# Un_Battery_old.net
KiCad netlist of a schematic drawn in EAGLE
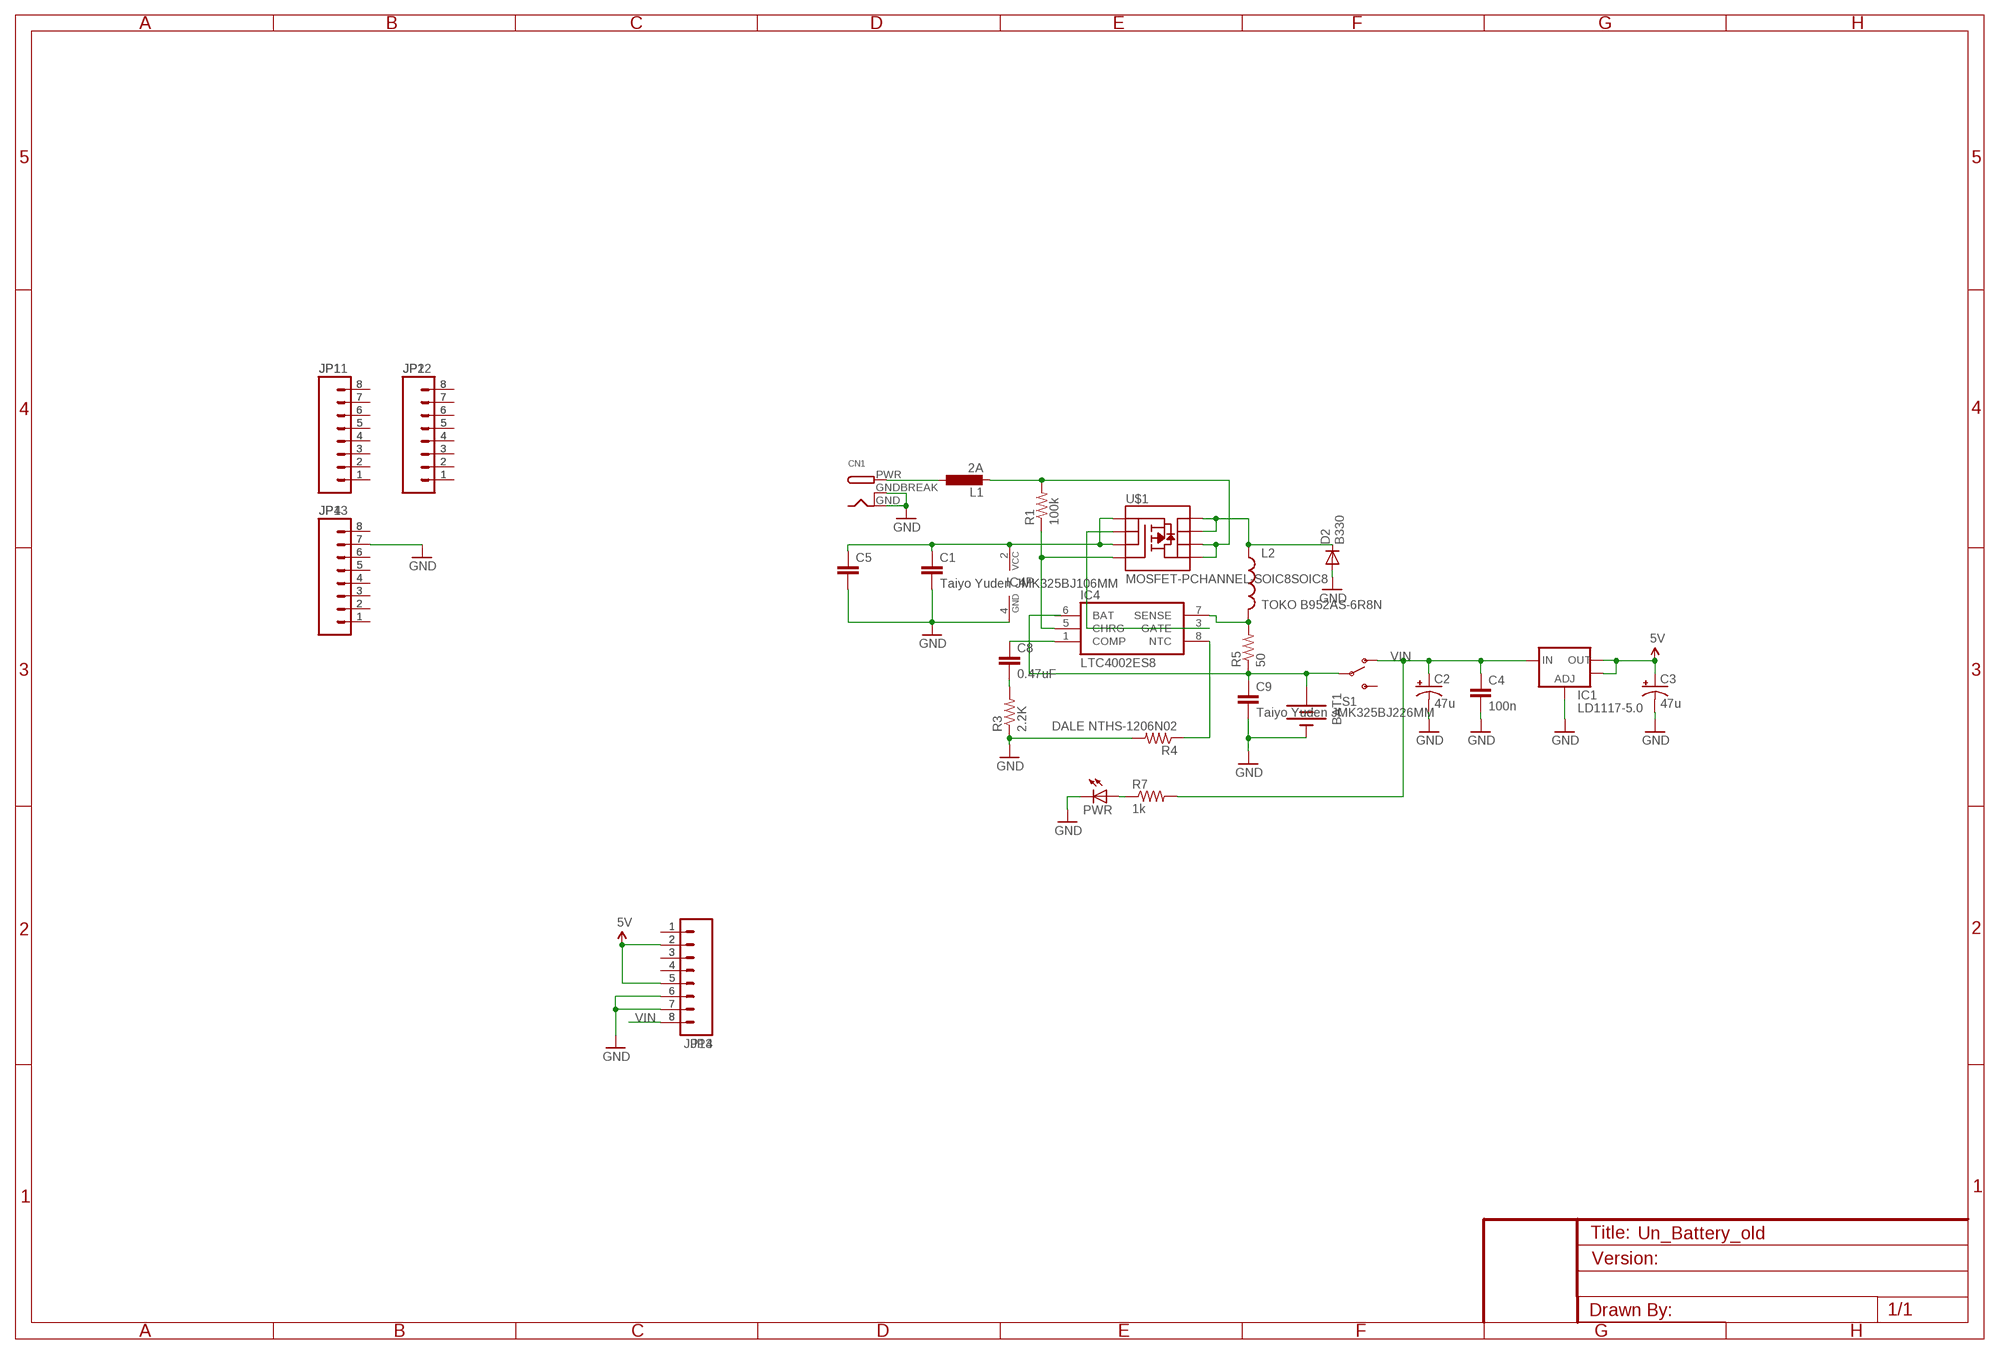
[diagram p0: schematic, sheet 1]

(export (version "E")
  (design (tool "Eeschema 10.0.6"))
  (components
    (comp (ref "BAT1")
      (value "BATTERYLIPO")
      (footprint "eagle-import:BATTERY-LIPO")
      (libsource (lib "eagle-import") (part "BATTERYLIPO"))
    )
    (comp (ref "C1")
      (value "Taiyo Yuden JMK325BJ106MM")
      (footprint "eagle-import:1206")
      (libsource (lib "eagle-import") (part "2SparkFun_CAP1206"))
    )
    (comp (ref "C2")
      (value "47u")
      (footprint "eagle-import:PANASONIC_D")
      (libsource (lib "eagle-import") (part "CAP_POLD"))
    )
    (comp (ref "C3")
      (value "47u")
      (footprint "eagle-import:PANASONIC_D")
      (libsource (lib "eagle-import") (part "CAP_POLD"))
    )
    (comp (ref "C4")
      (value "100n")
      (footprint "eagle-import:0603-CAP")
      (libsource (lib "eagle-import") (part "CAP0603-CAP"))
    )
    (comp (ref "C5")
      (value "CAP1206")
      (footprint "eagle-import:1206")
      (libsource (lib "eagle-import") (part "2SparkFun_CAP1206"))
    )
    (comp (ref "C8")
      (value "0.47uF")
      (footprint "eagle-import:1206")
      (libsource (lib "eagle-import") (part "2SparkFun_CAP1206"))
    )
    (comp (ref "C9")
      (value "Taiyo Yuden JMK325BJ226MM")
      (footprint "eagle-import:1206")
      (libsource (lib "eagle-import") (part "2SparkFun_CAP1206"))
    )
    (comp (ref "CN1")
      (value "DCBARRELPTH")
      (footprint "eagle-import:DCJACK_2MM_PTH")
      (libsource (lib "eagle-import") (part "DCBARRELPTH"))
    )
    (comp (ref "D2")
      (value "B330")
      (footprint "eagle-import:SMA-DIODE")
      (libsource (lib "eagle-import") (part "DIODESMA"))
    )
    (comp (ref "IC1")
      (value "LD1117-5.0")
      (footprint "eagle-import:SOT223")
      (libsource (lib "eagle-import") (part "V_REG_LM1117SOT223"))
    )
    (comp (ref "IC4")
      (value "LTC4002ES8")
      (footprint "eagle-import:SO08")
      (libsource (lib "eagle-import") (part "LTC4002S8E"))
    )
    (comp (ref "JP1")
      (value "M08SMD")
      (footprint "eagle-import:1X08-SMD")
      (libsource (lib "eagle-import") (part "M08SMD"))
    )
    (comp (ref "JP2")
      (value "M08SMD")
      (footprint "eagle-import:1X08-SMD")
      (libsource (lib "eagle-import") (part "M08SMD"))
    )
    (comp (ref "JP3")
      (value "M08SMD")
      (footprint "eagle-import:1X08-SMD")
      (libsource (lib "eagle-import") (part "M08SMD"))
    )
    (comp (ref "JP4")
      (value "M08SMD")
      (footprint "eagle-import:1X08-SMD")
      (libsource (lib "eagle-import") (part "M08SMD"))
    )
    (comp (ref "JP11")
      (value "M08SMD")
      (footprint "eagle-import:1X08-SMD")
      (libsource (lib "eagle-import") (part "M08SMD"))
    )
    (comp (ref "JP12")
      (value "M08SMD")
      (footprint "eagle-import:1X08-SMD")
      (libsource (lib "eagle-import") (part "M08SMD"))
    )
    (comp (ref "JP13")
      (value "M08SMD")
      (footprint "eagle-import:1X08-SMD")
      (libsource (lib "eagle-import") (part "M08SMD"))
    )
    (comp (ref "JP14")
      (value "M08SMD")
      (footprint "eagle-import:1X08-SMD")
      (libsource (lib "eagle-import") (part "M08SMD"))
    )
    (comp (ref "L1")
      (value "2A")
      (footprint "eagle-import:L1812")
      (libsource (lib "eagle-import") (part "L-EUL1812"))
    )
    (comp (ref "L2")
      (value "TOKO B952AS-6R8N")
      (footprint "eagle-import:CR75")
      (libsource (lib "eagle-import") (part "INDUCTORCR75"))
    )
    (comp (ref "PWR")
      (value "LED0805")
      (footprint "eagle-import:LED-0805")
      (libsource (lib "eagle-import") (part "LED0805"))
    )
    (comp (ref "R1")
      (value "100k")
      (footprint "eagle-import:1206")
      (libsource (lib "eagle-import") (part "RESISTOR1206"))
    )
    (comp (ref "R3")
      (value "2.2K")
      (footprint "eagle-import:1206")
      (libsource (lib "eagle-import") (part "RESISTOR1206"))
    )
    (comp (ref "R4")
      (value "DALE NTHS-1206N02")
      (footprint "eagle-import:1206")
      (libsource (lib "eagle-import") (part "RESISTOR1206"))
    )
    (comp (ref "R5")
      (value "50")
      (footprint "eagle-import:1206")
      (libsource (lib "eagle-import") (part "RESISTOR1206"))
    )
    (comp (ref "R7")
      (value "1k")
      (footprint "eagle-import:0805")
      (libsource (lib "eagle-import") (part "RESISTOR0805-RES"))
    )
    (comp (ref "S1")
      (value "SWITCH-SPSTSMD2")
      (footprint "eagle-import:SWITCH-SPDT-SMD")
      (libsource (lib "eagle-import") (part "SWITCH-SPSTSMD2"))
    )
    (comp (ref "U$1")
      (value "MOSFET-PCHANNEL-SOIC8SOIC8")
      (footprint "eagle-import:SO08")
      (libsource (lib "eagle-import") (part "MOSFET-PCHANNEL-SOIC8SOIC8"))
    )
  )
  (nets
    (net (code "1") (name "/VIN") (class "Default")
      (node (ref "C2") (pin "+") (pinfunction "+_+") (pintype "passive"))
      (node (ref "C4") (pin "1") (pinfunction "1_1") (pintype "passive"))
      (node (ref "IC1") (pin "3") (pinfunction "IN_3") (pintype "input"))
      (node (ref "JP14") (pin "8") (pinfunction "8_8") (pintype "passive"))
      (node (ref "JP3") (pin "8") (pinfunction "8_8") (pintype "passive"))
      (node (ref "R7") (pin "2") (pinfunction "2_2") (pintype "passive"))
      (node (ref "S1") (pin "1") (pinfunction "O_1") (pintype "passive"))
    )
    (net (code "2") (name "5V") (class "Default")
      (node (ref "C3") (pin "+") (pinfunction "+_+") (pintype "passive"))
      (node (ref "IC1") (pin "2") (pinfunction "OUT_2") (pintype "output"))
      (node (ref "IC1") (pin "4") (pinfunction "OUT_4") (pintype "output"))
      (node (ref "JP14") (pin "2") (pinfunction "2_2") (pintype "passive"))
      (node (ref "JP14") (pin "5") (pinfunction "5_5") (pintype "passive"))
      (node (ref "JP3") (pin "2") (pinfunction "2_2") (pintype "passive"))
      (node (ref "JP3") (pin "5") (pinfunction "5_5") (pintype "passive"))
    )
    (net (code "3") (name "GND") (class "Default")
      (node (ref "BAT1") (pin "-") (pinfunction "-_-") (pintype "power_in"))
      (node (ref "C1") (pin "2") (pinfunction "2_2") (pintype "passive"))
      (node (ref "C2") (pin "-") (pinfunction "-_-") (pintype "passive"))
      (node (ref "C3") (pin "-") (pinfunction "-_-") (pintype "passive"))
      (node (ref "C4") (pin "2") (pinfunction "2_2") (pintype "passive"))
      (node (ref "C5") (pin "2") (pinfunction "2_2") (pintype "passive"))
      (node (ref "C9") (pin "2") (pinfunction "2_2") (pintype "passive"))
      (node (ref "CN1") (pin "GND") (pinfunction "GND_GND") (pintype "power_in"))
      (node (ref "CN1") (pin "GNDBREAK") (pinfunction "GNDBREAK_GNDBREAK") (pintype "power_in"))
      (node (ref "D2") (pin "A") (pinfunction "A_A") (pintype "passive"))
      (node (ref "IC1") (pin "1") (pinfunction "ADJ_1") (pintype "input"))
      (node (ref "IC4") (pin "4") (pinfunction "GND_4") (pintype "power_in"))
      (node (ref "JP13") (pin "7") (pinfunction "7_7") (pintype "passive"))
      (node (ref "JP14") (pin "6") (pinfunction "6_6") (pintype "passive"))
      (node (ref "JP14") (pin "7") (pinfunction "7_7") (pintype "passive"))
      (node (ref "JP3") (pin "6") (pinfunction "6_6") (pintype "passive"))
      (node (ref "JP3") (pin "7") (pinfunction "7_7") (pintype "passive"))
      (node (ref "JP4") (pin "7") (pinfunction "7_7") (pintype "passive"))
      (node (ref "PWR") (pin "2") (pinfunction "C_2") (pintype "passive"))
      (node (ref "R3") (pin "1") (pinfunction "1_1") (pintype "passive"))
      (node (ref "R4") (pin "2") (pinfunction "2_2") (pintype "passive"))
    )
    (net (code "4") (name "Net-(C8-Pad2)") (class "Default")
      (node (ref "C8") (pin "2") (pinfunction "2_2") (pintype "passive"))
      (node (ref "R3") (pin "2") (pinfunction "2_2") (pintype "passive"))
    )
    (net (code "5") (name "Net-(CN1-PadPWR)") (class "Default")
      (node (ref "CN1") (pin "PWR") (pinfunction "PWR_PWR") (pintype "power_in"))
      (node (ref "L1") (pin "1") (pinfunction "1_1") (pintype "passive"))
    )
    (net (code "6") (name "Net-(IC4A-CHRG)") (class "Default")
      (node (ref "IC4") (pin "5") (pinfunction "CHRG_5") (pintype "bidirectional"))
      (node (ref "R1") (pin "1") (pinfunction "1_1") (pintype "passive"))
      (node (ref "U$1") (pin "4") (pinfunction "G_4") (pintype "bidirectional"))
    )
    (net (code "7") (name "Net-(IC4A-COMP)") (class "Default")
      (node (ref "C8") (pin "1") (pinfunction "1_1") (pintype "passive"))
      (node (ref "IC4") (pin "1") (pinfunction "COMP_1") (pintype "passive"))
    )
    (net (code "8") (name "Net-(IC4A-GATE)") (class "Default")
      (node (ref "IC4") (pin "3") (pinfunction "GATE_3") (pintype "output"))
      (node (ref "U$1") (pin "2") (pinfunction "S_2") (pintype "bidirectional"))
    )
    (net (code "9") (name "Net-(IC4A-NTC)") (class "Default")
      (node (ref "IC4") (pin "8") (pinfunction "NTC_8") (pintype "passive"))
      (node (ref "R4") (pin "1") (pinfunction "1_1") (pintype "passive"))
    )
    (net (code "10") (name "Net-(IC4A-SENSE)") (class "Default")
      (node (ref "IC4") (pin "7") (pinfunction "SENSE_7") (pintype "input"))
      (node (ref "L2") (pin "P$2") (pinfunction "2_P$2") (pintype "passive"))
      (node (ref "R5") (pin "2") (pinfunction "2_2") (pintype "passive"))
    )
    (net (code "11") (name "Net-(IC4B-VCC)") (class "Default")
      (node (ref "C1") (pin "1") (pinfunction "1_1") (pintype "passive"))
      (node (ref "C5") (pin "1") (pinfunction "1_1") (pintype "passive"))
      (node (ref "IC4") (pin "2") (pinfunction "VCC_2") (pintype "power_in"))
      (node (ref "U$1") (pin "1") (pinfunction "S_1") (pintype "bidirectional"))
      (node (ref "U$1") (pin "3") (pinfunction "S_3") (pintype "bidirectional"))
    )
    (net (code "12") (name "Net-(JP1-Pad1)") (class "Default")
      (node (ref "JP1") (pin "1") (pinfunction "1_1") (pintype "passive"))
      (node (ref "JP11") (pin "1") (pinfunction "1_1") (pintype "passive"))
    )
    (net (code "13") (name "Net-(JP1-Pad2)") (class "Default")
      (node (ref "JP1") (pin "2") (pinfunction "2_2") (pintype "passive"))
      (node (ref "JP11") (pin "2") (pinfunction "2_2") (pintype "passive"))
    )
    (net (code "14") (name "Net-(JP1-Pad3)") (class "Default")
      (node (ref "JP1") (pin "3") (pinfunction "3_3") (pintype "passive"))
      (node (ref "JP11") (pin "3") (pinfunction "3_3") (pintype "passive"))
    )
    (net (code "15") (name "Net-(JP1-Pad4)") (class "Default")
      (node (ref "JP1") (pin "4") (pinfunction "4_4") (pintype "passive"))
      (node (ref "JP11") (pin "4") (pinfunction "4_4") (pintype "passive"))
    )
    (net (code "16") (name "Net-(JP1-Pad5)") (class "Default")
      (node (ref "JP1") (pin "5") (pinfunction "5_5") (pintype "passive"))
      (node (ref "JP11") (pin "5") (pinfunction "5_5") (pintype "passive"))
    )
    (net (code "17") (name "Net-(JP1-Pad6)") (class "Default")
      (node (ref "JP1") (pin "6") (pinfunction "6_6") (pintype "passive"))
      (node (ref "JP11") (pin "6") (pinfunction "6_6") (pintype "passive"))
    )
    (net (code "18") (name "Net-(JP1-Pad7)") (class "Default")
      (node (ref "JP1") (pin "7") (pinfunction "7_7") (pintype "passive"))
      (node (ref "JP11") (pin "7") (pinfunction "7_7") (pintype "passive"))
    )
    (net (code "19") (name "Net-(JP1-Pad8)") (class "Default")
      (node (ref "JP1") (pin "8") (pinfunction "8_8") (pintype "passive"))
      (node (ref "JP11") (pin "8") (pinfunction "8_8") (pintype "passive"))
    )
    (net (code "20") (name "Net-(JP12-Pad1)") (class "Default")
      (node (ref "JP12") (pin "1") (pinfunction "1_1") (pintype "passive"))
      (node (ref "JP2") (pin "1") (pinfunction "1_1") (pintype "passive"))
    )
    (net (code "21") (name "Net-(JP12-Pad2)") (class "Default")
      (node (ref "JP12") (pin "2") (pinfunction "2_2") (pintype "passive"))
      (node (ref "JP2") (pin "2") (pinfunction "2_2") (pintype "passive"))
    )
    (net (code "22") (name "Net-(JP12-Pad3)") (class "Default")
      (node (ref "JP12") (pin "3") (pinfunction "3_3") (pintype "passive"))
      (node (ref "JP2") (pin "3") (pinfunction "3_3") (pintype "passive"))
    )
    (net (code "23") (name "Net-(JP12-Pad4)") (class "Default")
      (node (ref "JP12") (pin "4") (pinfunction "4_4") (pintype "passive"))
      (node (ref "JP2") (pin "4") (pinfunction "4_4") (pintype "passive"))
    )
    (net (code "24") (name "Net-(JP12-Pad5)") (class "Default")
      (node (ref "JP12") (pin "5") (pinfunction "5_5") (pintype "passive"))
      (node (ref "JP2") (pin "5") (pinfunction "5_5") (pintype "passive"))
    )
    (net (code "25") (name "Net-(JP12-Pad6)") (class "Default")
      (node (ref "JP12") (pin "6") (pinfunction "6_6") (pintype "passive"))
      (node (ref "JP2") (pin "6") (pinfunction "6_6") (pintype "passive"))
    )
    (net (code "26") (name "Net-(JP12-Pad7)") (class "Default")
      (node (ref "JP12") (pin "7") (pinfunction "7_7") (pintype "passive"))
      (node (ref "JP2") (pin "7") (pinfunction "7_7") (pintype "passive"))
    )
    (net (code "27") (name "Net-(JP12-Pad8)") (class "Default")
      (node (ref "JP12") (pin "8") (pinfunction "8_8") (pintype "passive"))
      (node (ref "JP2") (pin "8") (pinfunction "8_8") (pintype "passive"))
    )
    (net (code "28") (name "Net-(JP13-Pad1)") (class "Default")
      (node (ref "JP13") (pin "1") (pinfunction "1_1") (pintype "passive"))
      (node (ref "JP4") (pin "1") (pinfunction "1_1") (pintype "passive"))
    )
    (net (code "29") (name "Net-(JP13-Pad2)") (class "Default")
      (node (ref "JP13") (pin "2") (pinfunction "2_2") (pintype "passive"))
      (node (ref "JP4") (pin "2") (pinfunction "2_2") (pintype "passive"))
    )
    (net (code "30") (name "Net-(JP13-Pad3)") (class "Default")
      (node (ref "JP13") (pin "3") (pinfunction "3_3") (pintype "passive"))
      (node (ref "JP4") (pin "3") (pinfunction "3_3") (pintype "passive"))
    )
    (net (code "31") (name "Net-(JP13-Pad4)") (class "Default")
      (node (ref "JP13") (pin "4") (pinfunction "4_4") (pintype "passive"))
      (node (ref "JP4") (pin "4") (pinfunction "4_4") (pintype "passive"))
    )
    (net (code "32") (name "Net-(JP13-Pad5)") (class "Default")
      (node (ref "JP13") (pin "5") (pinfunction "5_5") (pintype "passive"))
      (node (ref "JP4") (pin "5") (pinfunction "5_5") (pintype "passive"))
    )
    (net (code "33") (name "Net-(JP13-Pad6)") (class "Default")
      (node (ref "JP13") (pin "6") (pinfunction "6_6") (pintype "passive"))
      (node (ref "JP4") (pin "6") (pinfunction "6_6") (pintype "passive"))
    )
    (net (code "34") (name "Net-(JP13-Pad8)") (class "Default")
      (node (ref "JP13") (pin "8") (pinfunction "8_8") (pintype "passive"))
      (node (ref "JP4") (pin "8") (pinfunction "8_8") (pintype "passive"))
    )
    (net (code "35") (name "Net-(JP14-Pad1)") (class "Default")
      (node (ref "JP14") (pin "1") (pinfunction "1_1") (pintype "passive"))
      (node (ref "JP3") (pin "1") (pinfunction "1_1") (pintype "passive"))
    )
    (net (code "36") (name "Net-(JP14-Pad3)") (class "Default")
      (node (ref "JP14") (pin "3") (pinfunction "3_3") (pintype "passive"))
      (node (ref "JP3") (pin "3") (pinfunction "3_3") (pintype "passive"))
    )
    (net (code "37") (name "Net-(JP14-Pad4)") (class "Default")
      (node (ref "JP14") (pin "4") (pinfunction "4_4") (pintype "passive"))
      (node (ref "JP3") (pin "4") (pinfunction "4_4") (pintype "passive"))
    )
    (net (code "38") (name "Net-(L1-Pad2)") (class "Default")
      (node (ref "L1") (pin "2") (pinfunction "2_2") (pintype "passive"))
      (node (ref "R1") (pin "2") (pinfunction "2_2") (pintype "passive"))
      (node (ref "U$1") (pin "5") (pinfunction "D_5") (pintype "bidirectional"))
      (node (ref "U$1") (pin "6") (pinfunction "D_6") (pintype "bidirectional"))
    )
    (net (code "39") (name "Net-(L2-1)") (class "Default")
      (node (ref "D2") (pin "C") (pinfunction "C_C") (pintype "passive"))
      (node (ref "L2") (pin "P$1") (pinfunction "1_P$1") (pintype "passive"))
      (node (ref "U$1") (pin "7") (pinfunction "D_7") (pintype "bidirectional"))
      (node (ref "U$1") (pin "8") (pinfunction "D_8") (pintype "bidirectional"))
    )
    (net (code "40") (name "Net-(PWR-A)") (class "Default")
      (node (ref "PWR") (pin "1") (pinfunction "A_1") (pintype "passive"))
      (node (ref "R7") (pin "1") (pinfunction "1_1") (pintype "passive"))
    )
    (net (code "41") (name "Net-(S1-P)") (class "Default")
      (node (ref "BAT1") (pin "+") (pinfunction "+_+") (pintype "power_in"))
      (node (ref "C9") (pin "1") (pinfunction "1_1") (pintype "passive"))
      (node (ref "R5") (pin "1") (pinfunction "1_1") (pintype "passive"))
      (node (ref "S1") (pin "2") (pinfunction "P_2") (pintype "passive"))
    )
    (net (code "42") (name "unconnected-(IC4A-BAT-Pad6)") (class "Default")
      (node (ref "IC4") (pin "6") (pinfunction "BAT_6") (pintype "passive"))
    )
    (net (code "43") (name "unconnected-(S1-S-Pad3)") (class "Default")
      (node (ref "S1") (pin "3") (pinfunction "S_3") (pintype "passive"))
    )
  )
)
